# lipo_fuel_gauge-v11.net
KiCad netlist of a schematic drawn in EAGLE
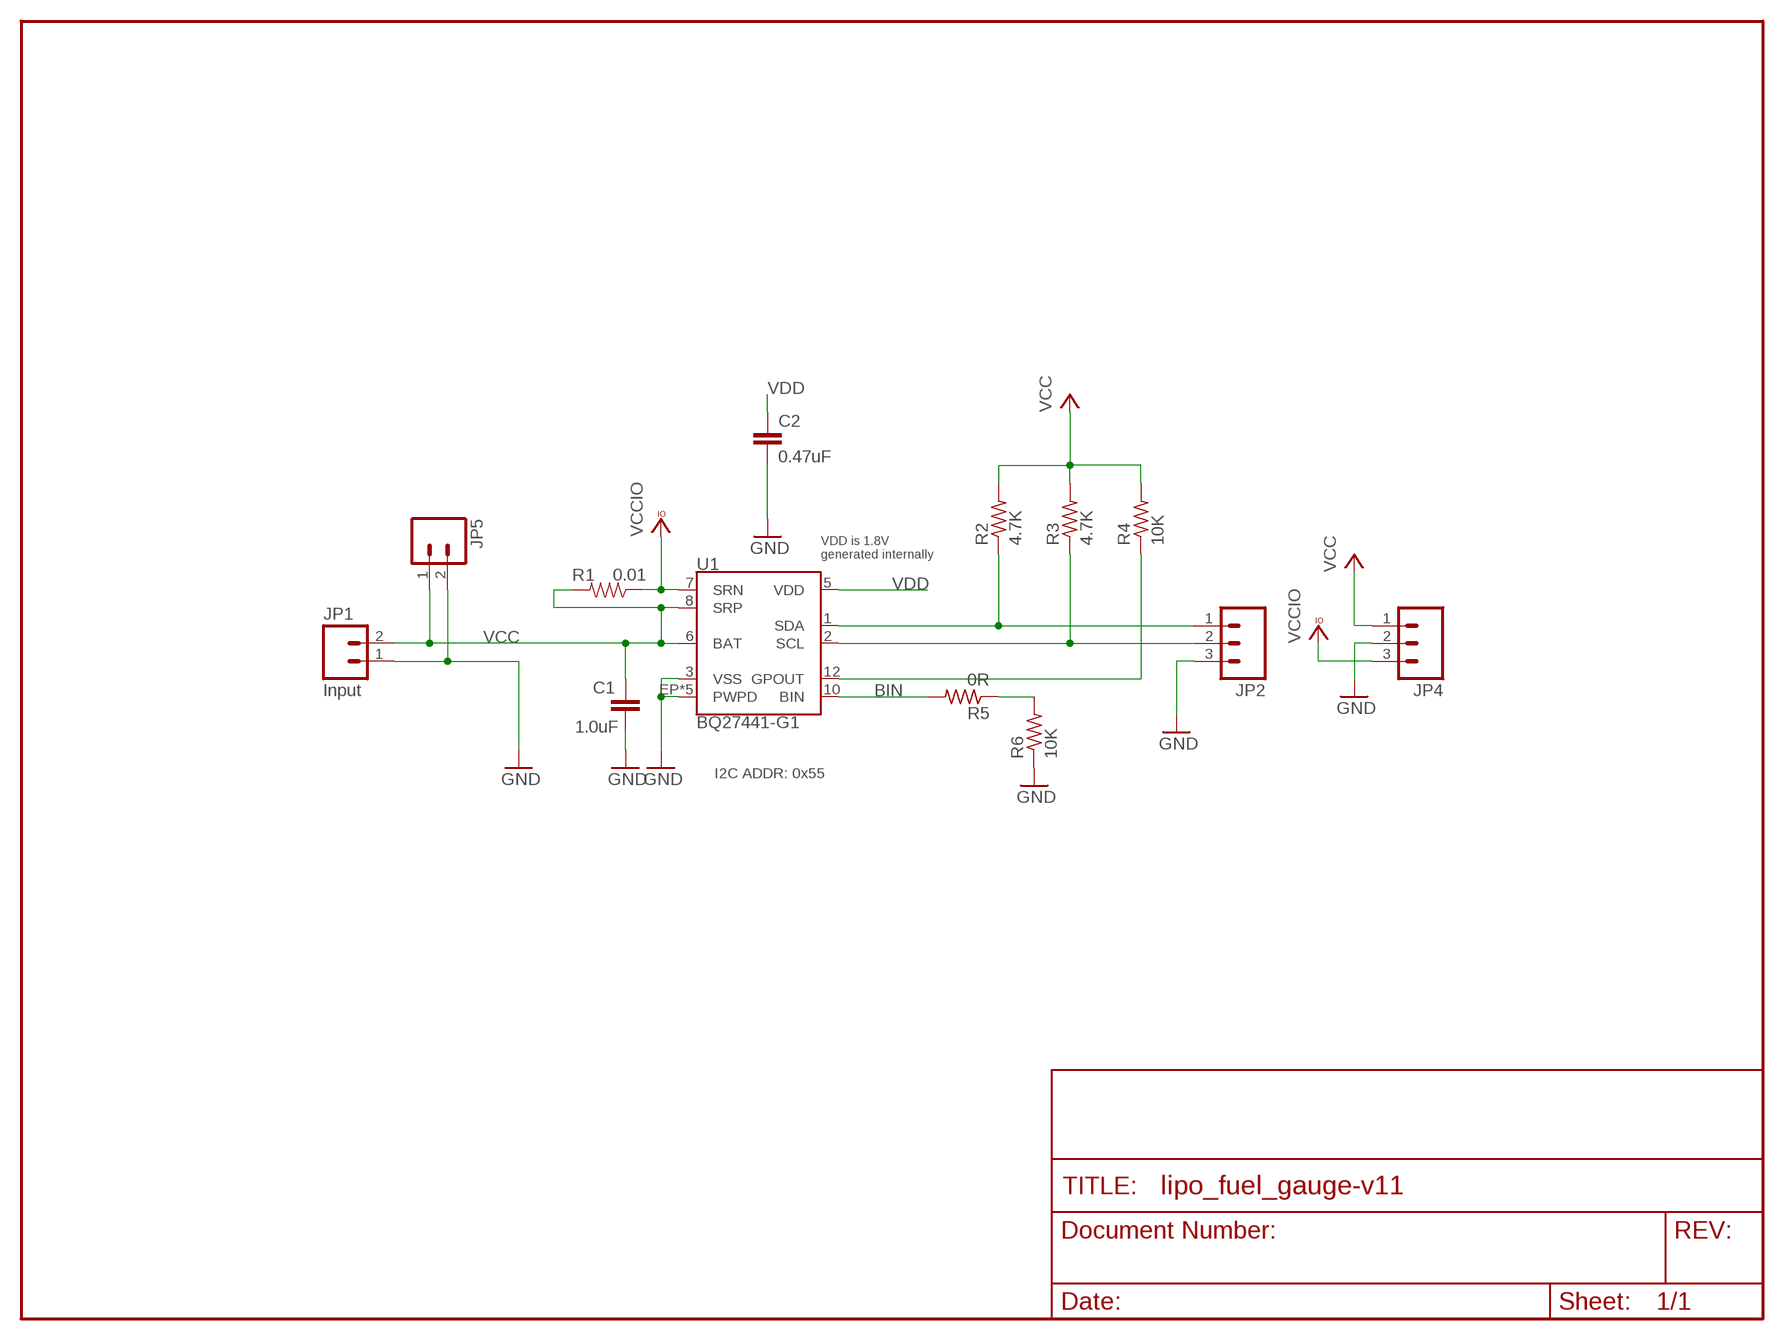
[diagram p0: schematic, sheet 1]

(export (version "E")
  (design (tool "Eeschema 10.0.6"))
  (components
    (comp (ref "C1")
      (value "1.0uF")
      (footprint "eagle-import:C0805")
      (libsource (lib "eagle-import") (part "C-EUC0805"))
    )
    (comp (ref "C2")
      (value "0.47uF")
      (footprint "eagle-import:C0805")
      (libsource (lib "eagle-import") (part "C-EUC0805"))
    )
    (comp (ref "JP1")
      (value "Input")
      (footprint "eagle-import:JST-2-SMD")
      (libsource (lib "eagle-import") (part "M02-JST-2MM-SMT"))
    )
    (comp (ref "JP2")
      (value "M03PTH")
      (footprint "eagle-import:1X03")
      (libsource (lib "eagle-import") (part "M03PTH"))
    )
    (comp (ref "JP4")
      (value "M03PTH")
      (footprint "eagle-import:1X03")
      (libsource (lib "eagle-import") (part "M03PTH"))
    )
    (comp (ref "JP5")
      (value "M02PTH")
      (footprint "eagle-import:1X02")
      (libsource (lib "eagle-import") (part "M02PTH"))
    )
    (comp (ref "R1")
      (value "0.01")
      (footprint "eagle-import:1206")
      (libsource (lib "eagle-import") (part "RESISTOR1206"))
    )
    (comp (ref "R2")
      (value "4.7K")
      (footprint "eagle-import:R0805")
      (libsource (lib "eagle-import") (part "R-US_R0805"))
    )
    (comp (ref "R3")
      (value "4.7K")
      (footprint "eagle-import:R0805")
      (libsource (lib "eagle-import") (part "R-US_R0805"))
    )
    (comp (ref "R4")
      (value "10K")
      (footprint "eagle-import:R0805")
      (libsource (lib "eagle-import") (part "R-US_R0805"))
    )
    (comp (ref "R5")
      (value "0R")
      (footprint "eagle-import:R0805")
      (libsource (lib "eagle-import") (part "R-US_R0805"))
    )
    (comp (ref "R6")
      (value "10K")
      (footprint "eagle-import:R0805")
      (libsource (lib "eagle-import") (part "R-US_R0805"))
    )
    (comp (ref "U1")
      (value "BQ27441-G1")
      (footprint "eagle-import:PDSO-N12")
      (libsource (lib "eagle-import") (part "BQ27441-G1"))
    )
  )
  (nets
    (net (code "1") (name "/BIN") (class "Default")
      (node (ref "R5") (pin "2") (pinfunction "2_2") (pintype "passive"))
      (node (ref "U1") (pin "10") (pinfunction "BIN_10") (pintype "bidirectional"))
    )
    (net (code "2") (name "/VDD") (class "Default")
      (node (ref "C2") (pin "1") (pinfunction "1_1") (pintype "passive"))
      (node (ref "U1") (pin "5") (pinfunction "VDD_5") (pintype "bidirectional"))
    )
    (net (code "3") (name "GND") (class "Default")
      (node (ref "C1") (pin "2") (pinfunction "2_2") (pintype "passive"))
      (node (ref "C2") (pin "2") (pinfunction "2_2") (pintype "passive"))
      (node (ref "JP1") (pin "1") (pinfunction "1_1") (pintype "passive"))
      (node (ref "JP2") (pin "3") (pinfunction "3_3") (pintype "passive"))
      (node (ref "JP4") (pin "2") (pinfunction "2_2") (pintype "passive"))
      (node (ref "JP5") (pin "2") (pinfunction "2_2") (pintype "passive"))
      (node (ref "R6") (pin "1") (pinfunction "1_1") (pintype "passive"))
      (node (ref "U1") (pin "3") (pinfunction "VSS_3") (pintype "bidirectional"))
      (node (ref "U1") (pin "EP") (pinfunction "PWPD_EP") (pintype "bidirectional"))
      (node (ref "U1") (pin "EP1") (pinfunction "PWPD_EP1") (pintype "bidirectional"))
      (node (ref "U1") (pin "EP2") (pinfunction "PWPD_EP2") (pintype "bidirectional"))
      (node (ref "U1") (pin "EP3") (pinfunction "PWPD_EP3") (pintype "bidirectional"))
      (node (ref "U1") (pin "EP4") (pinfunction "PWPD_EP4") (pintype "bidirectional"))
    )
    (net (code "4") (name "Net-(R5-Pad1)") (class "Default")
      (node (ref "R5") (pin "1") (pinfunction "1_1") (pintype "passive"))
      (node (ref "R6") (pin "2") (pinfunction "2_2") (pintype "passive"))
    )
    (net (code "5") (name "Net-(U1-GPOUT)") (class "Default")
      (node (ref "R4") (pin "1") (pinfunction "1_1") (pintype "passive"))
      (node (ref "U1") (pin "12") (pinfunction "GPOUT_12") (pintype "bidirectional"))
    )
    (net (code "6") (name "Net-(U1-SCL)") (class "Default")
      (node (ref "JP2") (pin "2") (pinfunction "2_2") (pintype "passive"))
      (node (ref "R3") (pin "1") (pinfunction "1_1") (pintype "passive"))
      (node (ref "U1") (pin "2") (pinfunction "SCL_2") (pintype "bidirectional"))
    )
    (net (code "7") (name "Net-(U1-SDA)") (class "Default")
      (node (ref "JP2") (pin "1") (pinfunction "1_1") (pintype "passive"))
      (node (ref "R2") (pin "1") (pinfunction "1_1") (pintype "passive"))
      (node (ref "U1") (pin "1") (pinfunction "SDA_1") (pintype "bidirectional"))
    )
    (net (code "8") (name "VCC") (class "Default")
      (node (ref "C1") (pin "1") (pinfunction "1_1") (pintype "passive"))
      (node (ref "JP1") (pin "2") (pinfunction "2_2") (pintype "passive"))
      (node (ref "JP4") (pin "1") (pinfunction "1_1") (pintype "passive"))
      (node (ref "JP5") (pin "1") (pinfunction "1_1") (pintype "passive"))
      (node (ref "R1") (pin "2") (pinfunction "2_2") (pintype "passive"))
      (node (ref "R2") (pin "2") (pinfunction "2_2") (pintype "passive"))
      (node (ref "R3") (pin "2") (pinfunction "2_2") (pintype "passive"))
      (node (ref "R4") (pin "2") (pinfunction "2_2") (pintype "passive"))
      (node (ref "U1") (pin "6") (pinfunction "BAT_6") (pintype "bidirectional"))
      (node (ref "U1") (pin "8") (pinfunction "SRP_8") (pintype "bidirectional"))
    )
    (net (code "9") (name "VCCIO") (class "Default")
      (node (ref "JP4") (pin "3") (pinfunction "3_3") (pintype "passive"))
      (node (ref "R1") (pin "1") (pinfunction "1_1") (pintype "passive"))
      (node (ref "U1") (pin "7") (pinfunction "SRN_7") (pintype "bidirectional"))
    )
  )
)
